# bubbler.net
KiCad netlist of a schematic drawn in EAGLE
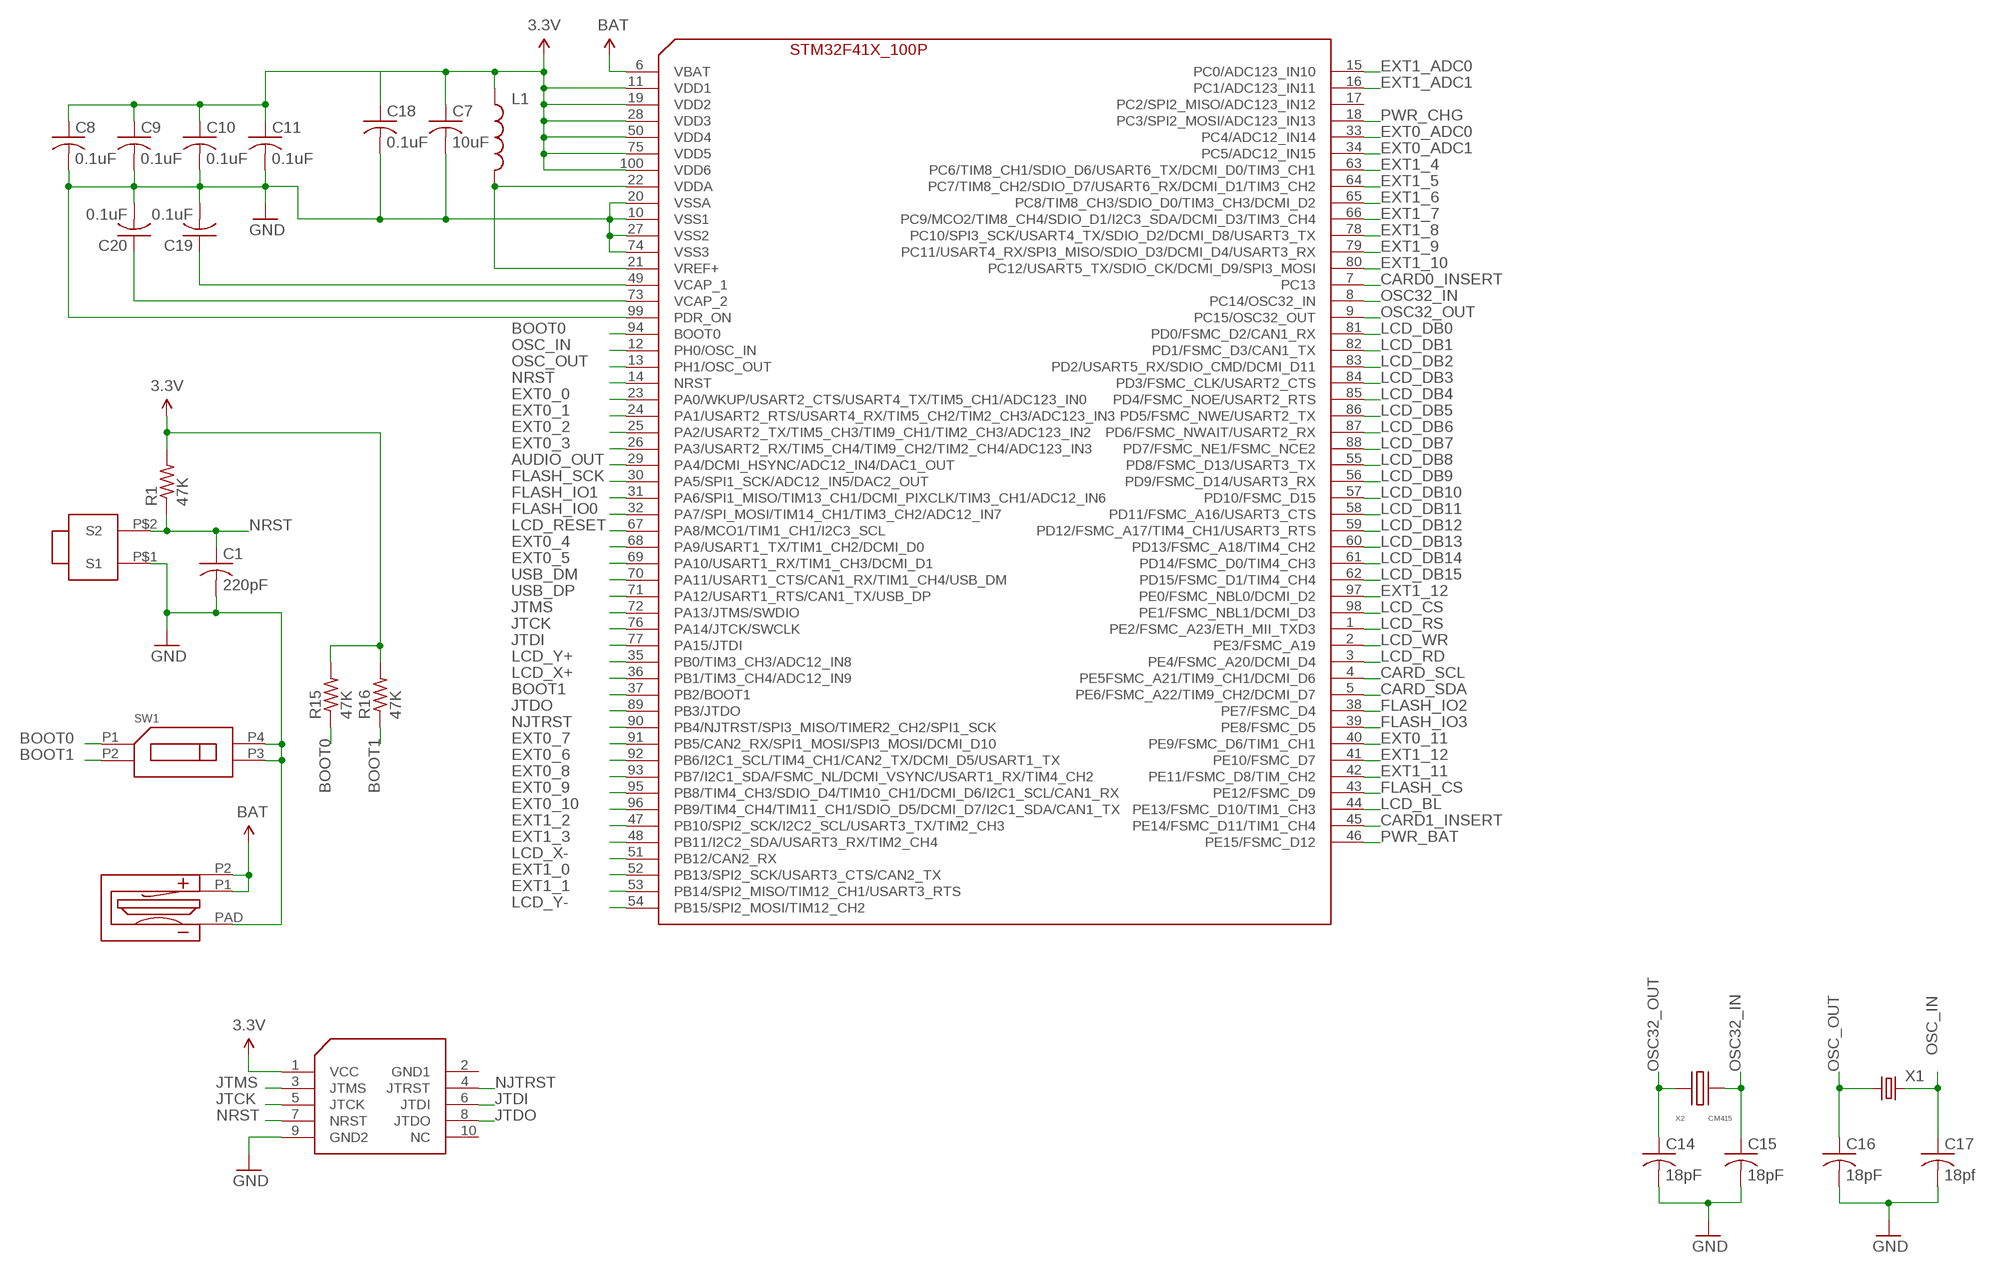
[diagram p0: schematic, sheet 1]
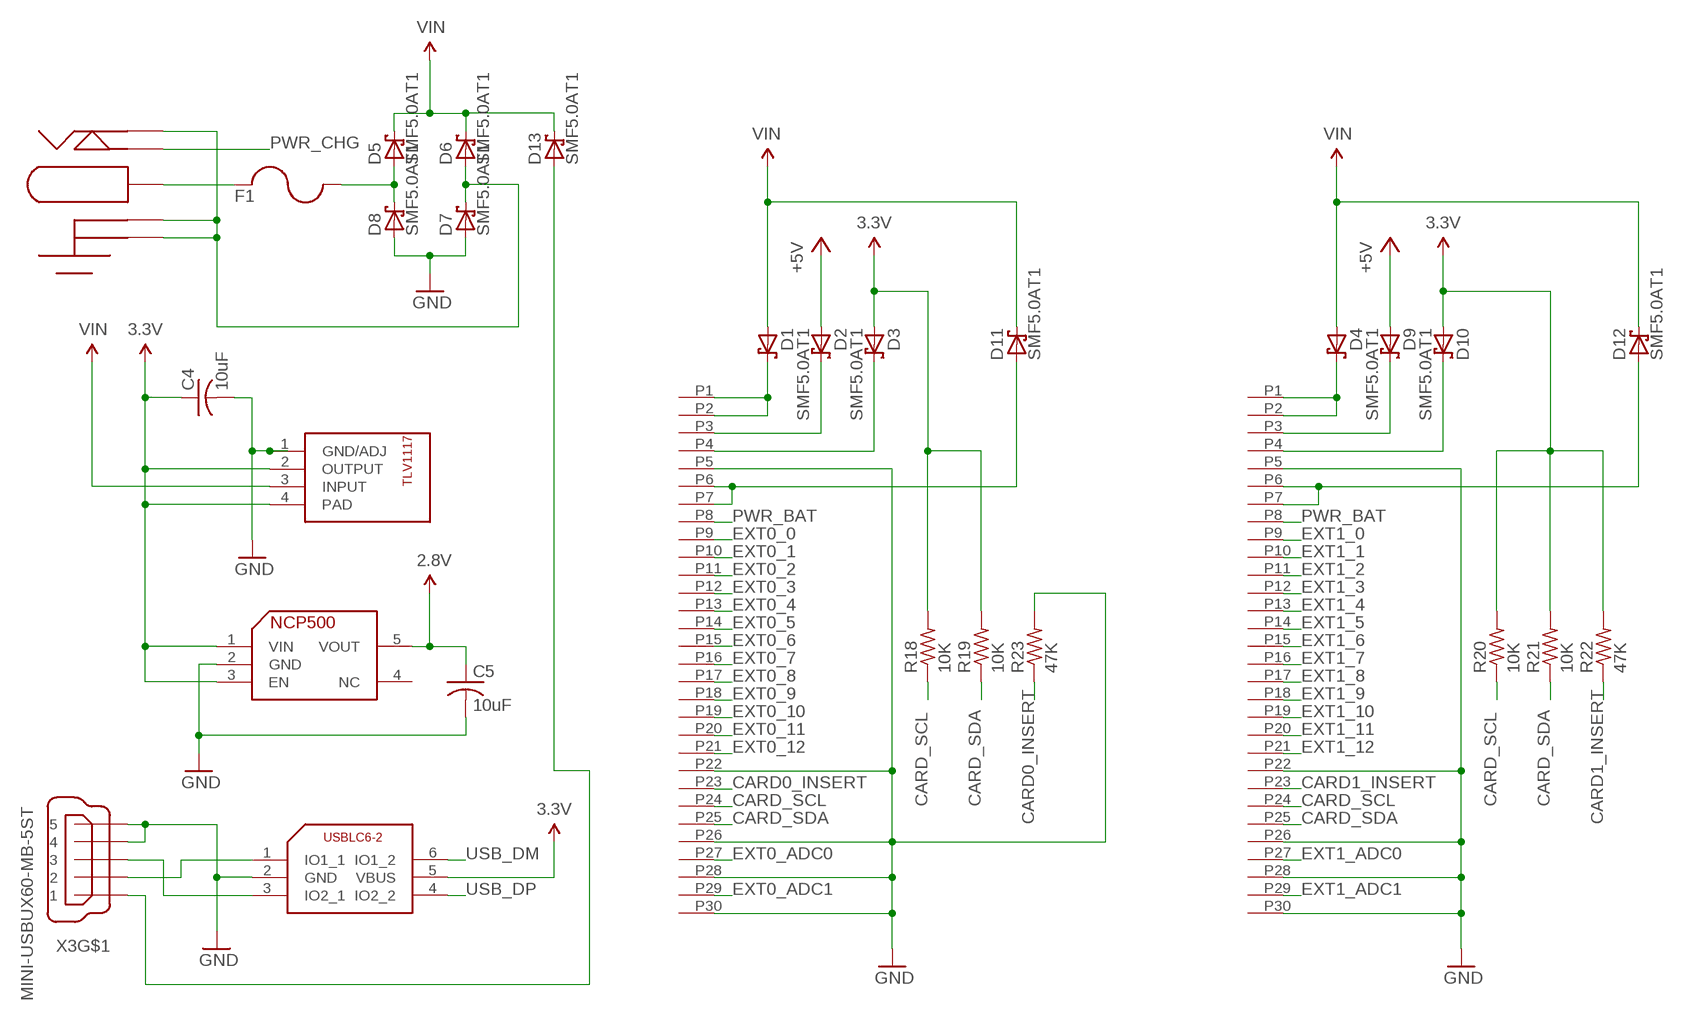
[diagram p1: schematic, sheet 2]
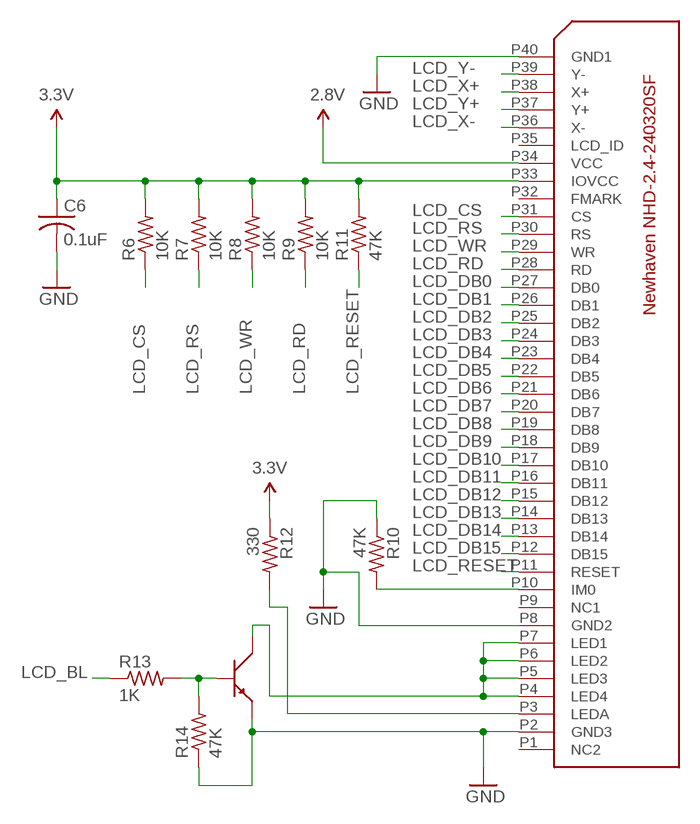
[diagram p2: schematic, sheet 3]
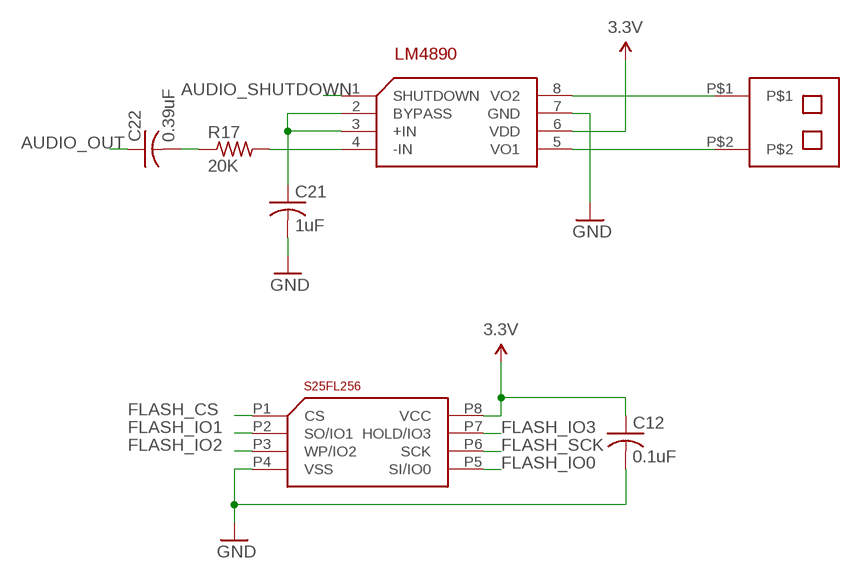
[diagram p3: schematic, sheet 4]

(export (version "E")
  (design (tool "Eeschema 10.0.6"))
  (components
    (comp (ref "B1")
      (value "BATTERY-LINX-HLD-001")
      (footprint "eagle-import:BATTERY-LINX-HLD-001")
      (libsource (lib "eagle-import") (part "BATTERY-LINX-HLD-001"))
    )
    (comp (ref "C1")
      (value "220pF")
      (footprint "eagle-import:C0402")
      (libsource (lib "eagle-import") (part "C-USC0402"))
    )
    (comp (ref "C7")
      (value "10uF")
      (footprint "eagle-import:C0805")
      (libsource (lib "eagle-import") (part "C-USC0805"))
    )
    (comp (ref "C8")
      (value "0.1uF")
      (footprint "eagle-import:C0402")
      (libsource (lib "eagle-import") (part "C-USC0402"))
    )
    (comp (ref "C9")
      (value "0.1uF")
      (footprint "eagle-import:C0402")
      (libsource (lib "eagle-import") (part "C-USC0402"))
    )
    (comp (ref "C10")
      (value "0.1uF")
      (footprint "eagle-import:C0402")
      (libsource (lib "eagle-import") (part "C-USC0402"))
    )
    (comp (ref "C11")
      (value "0.1uF")
      (footprint "eagle-import:C0402")
      (libsource (lib "eagle-import") (part "C-USC0402"))
    )
    (comp (ref "C14")
      (value "18pF")
      (footprint "eagle-import:C0402")
      (libsource (lib "eagle-import") (part "C-USC0402"))
    )
    (comp (ref "C15")
      (value "18pF")
      (footprint "eagle-import:C0402")
      (libsource (lib "eagle-import") (part "C-USC0402"))
    )
    (comp (ref "C16")
      (value "18pF")
      (footprint "eagle-import:C0402")
      (libsource (lib "eagle-import") (part "C-USC0402"))
    )
    (comp (ref "C17")
      (value "18pf")
      (footprint "eagle-import:C0402")
      (libsource (lib "eagle-import") (part "C-USC0402"))
    )
    (comp (ref "C18")
      (value "0.1uF")
      (footprint "eagle-import:C0402")
      (libsource (lib "eagle-import") (part "C-USC0402"))
    )
    (comp (ref "C19")
      (value "0.1uF")
      (footprint "eagle-import:C0402")
      (libsource (lib "eagle-import") (part "C-USC0402"))
    )
    (comp (ref "C20")
      (value "0.1uF")
      (footprint "eagle-import:C0402")
      (libsource (lib "eagle-import") (part "C-USC0402"))
    )
    (comp (ref "L1")
      (value "INDUCTOR0603")
      (footprint "eagle-import:0603")
      (libsource (lib "eagle-import") (part "INDUCTOR0603"))
    )
    (comp (ref "R1")
      (value "47K")
      (footprint "eagle-import:R0402")
      (libsource (lib "eagle-import") (part "R-US_R0402"))
    )
    (comp (ref "R15")
      (value "47K")
      (footprint "eagle-import:R0402")
      (libsource (lib "eagle-import") (part "R-US_R0402"))
    )
    (comp (ref "R16")
      (value "47K")
      (footprint "eagle-import:R0402")
      (libsource (lib "eagle-import") (part "R-US_R0402"))
    )
    (comp (ref "SW1")
      (value "SWITCH-DIP-GDH-02")
      (footprint "eagle-import:SWITCH-DIP-GDH-02")
      (libsource (lib "eagle-import") (part "SWITCH-DIP-GDH-02"))
    )
    (comp (ref "SW2")
      (value "ITT-SWITCH-KSS-G")
      (footprint "eagle-import:ITT-KSS-G")
      (libsource (lib "eagle-import") (part "ITT-SWITCH-KSS-G"))
    )
    (comp (ref "U$1")
      (value "STM32-JTAG-10P")
      (footprint "eagle-import:STM32-JTAG-10P")
      (libsource (lib "eagle-import") (part "STM32-JTAG-10P"))
    )
    (comp (ref "U1")
      (value "STM32F41X-100P")
      (footprint "eagle-import:TQFP100")
      (libsource (lib "eagle-import") (part "STM32F41X-100P"))
    )
    (comp (ref "X1")
      (value "CRYSTAL5X3")
      (footprint "eagle-import:CRYSTAL-SMD-5X3")
      (libsource (lib "eagle-import") (part "CRYSTAL5X3"))
    )
    (comp (ref "X2")
      (value "CM415")
      (footprint "eagle-import:CM415")
      (libsource (lib "eagle-import") (part "CM415"))
    )
    (comp (ref "C6")
      (value "0.1uF")
      (footprint "eagle-import:C0402")
      (libsource (lib "eagle-import") (part "C-USC0402"))
    )
    (comp (ref "R6")
      (value "10K")
      (footprint "eagle-import:R0402")
      (libsource (lib "eagle-import") (part "R-US_R0402"))
    )
    (comp (ref "R7")
      (value "10K")
      (footprint "eagle-import:R0402")
      (libsource (lib "eagle-import") (part "R-US_R0402"))
    )
    (comp (ref "R8")
      (value "10K")
      (footprint "eagle-import:R0402")
      (libsource (lib "eagle-import") (part "R-US_R0402"))
    )
    (comp (ref "R9")
      (value "10K")
      (footprint "eagle-import:R0402")
      (libsource (lib "eagle-import") (part "R-US_R0402"))
    )
    (comp (ref "R10")
      (value "47K")
      (footprint "eagle-import:R0402")
      (libsource (lib "eagle-import") (part "R-US_R0402"))
    )
    (comp (ref "R11")
      (value "47K")
      (footprint "eagle-import:R0402")
      (libsource (lib "eagle-import") (part "R-US_R0402"))
    )
    (comp (ref "R12")
      (value "330")
      (footprint "eagle-import:R1206")
      (libsource (lib "eagle-import") (part "R-US_R1206"))
    )
    (comp (ref "R13")
      (value "1K")
      (footprint "eagle-import:R0402")
      (libsource (lib "eagle-import") (part "R-US_R0402"))
    )
    (comp (ref "R14")
      (value "47K")
      (footprint "eagle-import:R0402")
      (libsource (lib "eagle-import") (part "R-US_R0402"))
    )
    (comp (ref "U$10")
      (value "NHD-2.4-240320SF")
      (footprint "eagle-import:MOLEX-534132-060")
      (libsource (lib "eagle-import") (part "NHD-2.4-240320SF"))
    )
    (comp (ref "U4")
      (value "BIPOLAR-PMBT6428")
      (footprint "eagle-import:DUBLIB_SOT23")
      (libsource (lib "eagle-import") (part "BIPOLAR-PMBT6428"))
    )
    (comp (ref "C4")
      (value "10uF")
      (footprint "eagle-import:C1206")
      (libsource (lib "eagle-import") (part "C-USC1206"))
    )
    (comp (ref "C5")
      (value "10uF")
      (footprint "eagle-import:C1206")
      (libsource (lib "eagle-import") (part "C-USC1206"))
    )
    (comp (ref "CARD0")
      (value "CONNECTOR-JAE-TX24-30F")
      (footprint "eagle-import:CONNECTOR-JAE-TX24-30")
      (libsource (lib "eagle-import") (part "CONNECTOR-JAE-TX24-30F"))
    )
    (comp (ref "CARD1")
      (value "CONNECTOR-JAE-TX24-30F")
      (footprint "eagle-import:CONNECTOR-JAE-TX24-30")
      (libsource (lib "eagle-import") (part "CONNECTOR-JAE-TX24-30F"))
    )
    (comp (ref "D1")
      (value "SCHOTTKY-DIODESMD")
      (footprint "eagle-import:SMB")
      (libsource (lib "eagle-import") (part "SCHOTTKY-DIODESMD"))
    )
    (comp (ref "D2")
      (value "SMF5.0AT1")
      (footprint "eagle-import:SOD123FL")
      (libsource (lib "eagle-import") (part "SMF5.0AT1"))
    )
    (comp (ref "D3")
      (value "SMF5.0AT1")
      (footprint "eagle-import:SOD123FL")
      (libsource (lib "eagle-import") (part "SMF5.0AT1"))
    )
    (comp (ref "D4")
      (value "SCHOTTKY-DIODESMD")
      (footprint "eagle-import:SMB")
      (libsource (lib "eagle-import") (part "SCHOTTKY-DIODESMD"))
    )
    (comp (ref "D5")
      (value "SMF5.0AT1")
      (footprint "eagle-import:SOD123FL")
      (libsource (lib "eagle-import") (part "SMF5.0AT1"))
    )
    (comp (ref "D6")
      (value "SMF5.0AT1")
      (footprint "eagle-import:SOD123FL")
      (libsource (lib "eagle-import") (part "SMF5.0AT1"))
    )
    (comp (ref "D7")
      (value "SMF5.0AT1")
      (footprint "eagle-import:SOD123FL")
      (libsource (lib "eagle-import") (part "SMF5.0AT1"))
    )
    (comp (ref "D8")
      (value "SMF5.0AT1")
      (footprint "eagle-import:SOD123FL")
      (libsource (lib "eagle-import") (part "SMF5.0AT1"))
    )
    (comp (ref "D9")
      (value "SMF5.0AT1")
      (footprint "eagle-import:SOD123FL")
      (libsource (lib "eagle-import") (part "SMF5.0AT1"))
    )
    (comp (ref "D10")
      (value "SMF5.0AT1")
      (footprint "eagle-import:SOD123FL")
      (libsource (lib "eagle-import") (part "SMF5.0AT1"))
    )
    (comp (ref "D11")
      (value "SMF5.0AT1")
      (footprint "eagle-import:SOD123FL")
      (libsource (lib "eagle-import") (part "SMF5.0AT1"))
    )
    (comp (ref "D12")
      (value "SMF5.0AT1")
      (footprint "eagle-import:SOD123FL")
      (libsource (lib "eagle-import") (part "SMF5.0AT1"))
    )
    (comp (ref "D13")
      (value "SMF5.0AT1")
      (footprint "eagle-import:SOD123FL")
      (libsource (lib "eagle-import") (part "SMF5.0AT1"))
    )
    (comp (ref "F1")
      (value "BOURNES-PTC-MF-SMXXXMF-SM030")
      (footprint "eagle-import:MF-SM030")
      (libsource (lib "eagle-import") (part "BOURNES-PTC-MF-SMXXXMF-SM030"))
    )
    (comp (ref "R18")
      (value "10K")
      (footprint "eagle-import:R0402")
      (libsource (lib "eagle-import") (part "R-US_R0402"))
    )
    (comp (ref "R19")
      (value "10K")
      (footprint "eagle-import:R0402")
      (libsource (lib "eagle-import") (part "R-US_R0402"))
    )
    (comp (ref "R20")
      (value "10K")
      (footprint "eagle-import:R0402")
      (libsource (lib "eagle-import") (part "R-US_R0402"))
    )
    (comp (ref "R21")
      (value "10K")
      (footprint "eagle-import:R0402")
      (libsource (lib "eagle-import") (part "R-US_R0402"))
    )
    (comp (ref "R22")
      (value "47K")
      (footprint "eagle-import:R0402")
      (libsource (lib "eagle-import") (part "R-US_R0402"))
    )
    (comp (ref "R23")
      (value "47K")
      (footprint "eagle-import:R0402")
      (libsource (lib "eagle-import") (part "R-US_R0402"))
    )
    (comp (ref "U$2")
      (value "DCJACK-CUI-PJ051AH")
      (footprint "eagle-import:DCJACK_CUI_PJ012B")
      (libsource (lib "eagle-import") (part "DCJACK-CUI-PJ051AH"))
    )
    (comp (ref "U$7")
      (value "NCP500")
      (footprint "eagle-import:SOT23-5L")
      (libsource (lib "eagle-import") (part "NCP500"))
    )
    (comp (ref "U5")
      (value "USBLC6-2")
      (footprint "eagle-import:SOT23-6L")
      (libsource (lib "eagle-import") (part "USBLC6-2"))
    )
    (comp (ref "U6")
      (value "TLV1117")
      (footprint "eagle-import:SOT223")
      (libsource (lib "eagle-import") (part "TLV1117"))
    )
    (comp (ref "X3")
      (value "MINI-USBUX60-MB-5ST")
      (footprint "eagle-import:DUBLIB_UX60-MB-5ST")
      (libsource (lib "eagle-import") (part "MINI-USBUX60-MB-5ST"))
    )
    (comp (ref "C12")
      (value "0.1uF")
      (footprint "eagle-import:C0402")
      (libsource (lib "eagle-import") (part "C-USC0402"))
    )
    (comp (ref "C21")
      (value "1uF")
      (footprint "eagle-import:C0402")
      (libsource (lib "eagle-import") (part "C-USC0402"))
    )
    (comp (ref "C22")
      (value "0.39uF")
      (footprint "eagle-import:C0402")
      (libsource (lib "eagle-import") (part "C-USC0402"))
    )
    (comp (ref "R17")
      (value "20K")
      (footprint "eagle-import:R0402")
      (libsource (lib "eagle-import") (part "R-US_R0402"))
    )
    (comp (ref "U2")
      (value "SPANSION-S25FL256")
      (footprint "eagle-import:SPANSION-WSON-8")
      (libsource (lib "eagle-import") (part "SPANSION-S25FL256"))
    )
    (comp (ref "U3")
      (value "LM4890")
      (footprint "eagle-import:TSSOP8")
      (libsource (lib "eagle-import") (part "LM4890"))
    )
    (comp (ref "U7")
      (value "MOLEX-1.25-WTB-RA-CONN-2POS")
      (footprint "eagle-import:MOLEX-1.25WTB-RA-CONN")
      (libsource (lib "eagle-import") (part "MOLEX-1.25-WTB-RA-CONN-2POS"))
    )
  )
  (nets
    (net (code "1") (name "+5V") (class "Default")
      (node (ref "D2") (pin "A") (pinfunction "A_A") (pintype "passive"))
      (node (ref "D9") (pin "A") (pinfunction "A_A") (pintype "passive"))
    )
    (net (code "2") (name "2.8V") (class "Default")
      (node (ref "C5") (pin "1") (pinfunction "1_1") (pintype "passive"))
      (node (ref "U$10") (pin "P34") (pinfunction "VCC_P34") (pintype "bidirectional"))
      (node (ref "U$7") (pin "5") (pinfunction "VOUT_5") (pintype "bidirectional"))
    )
    (net (code "3") (name "3.3V") (class "Default")
      (node (ref "C10") (pin "1") (pinfunction "1_1") (pintype "passive"))
      (node (ref "C11") (pin "1") (pinfunction "1_1") (pintype "passive"))
      (node (ref "C12") (pin "1") (pinfunction "1_1") (pintype "passive"))
      (node (ref "C18") (pin "1") (pinfunction "1_1") (pintype "passive"))
      (node (ref "C4") (pin "1") (pinfunction "1_1") (pintype "passive"))
      (node (ref "C6") (pin "1") (pinfunction "1_1") (pintype "passive"))
      (node (ref "C7") (pin "1") (pinfunction "1_1") (pintype "passive"))
      (node (ref "C8") (pin "1") (pinfunction "1_1") (pintype "passive"))
      (node (ref "C9") (pin "1") (pinfunction "1_1") (pintype "passive"))
      (node (ref "D10") (pin "A") (pinfunction "A_A") (pintype "passive"))
      (node (ref "D3") (pin "A") (pinfunction "A_A") (pintype "passive"))
      (node (ref "L1") (pin "1") (pinfunction "1_1") (pintype "passive"))
      (node (ref "R1") (pin "2") (pinfunction "2_2") (pintype "passive"))
      (node (ref "R11") (pin "2") (pinfunction "2_2") (pintype "passive"))
      (node (ref "R12") (pin "1") (pinfunction "1_1") (pintype "passive"))
      (node (ref "R15") (pin "2") (pinfunction "2_2") (pintype "passive"))
      (node (ref "R16") (pin "2") (pinfunction "2_2") (pintype "passive"))
      (node (ref "R18") (pin "2") (pinfunction "2_2") (pintype "passive"))
      (node (ref "R19") (pin "2") (pinfunction "2_2") (pintype "passive"))
      (node (ref "R20") (pin "2") (pinfunction "2_2") (pintype "passive"))
      (node (ref "R21") (pin "2") (pinfunction "2_2") (pintype "passive"))
      (node (ref "R22") (pin "2") (pinfunction "2_2") (pintype "passive"))
      (node (ref "R6") (pin "2") (pinfunction "2_2") (pintype "passive"))
      (node (ref "R7") (pin "2") (pinfunction "2_2") (pintype "passive"))
      (node (ref "R8") (pin "2") (pinfunction "2_2") (pintype "passive"))
      (node (ref "R9") (pin "2") (pinfunction "2_2") (pintype "passive"))
      (node (ref "U$1") (pin "1") (pinfunction "VCC_1") (pintype "bidirectional"))
      (node (ref "U$10") (pin "P33") (pinfunction "IOVCC_P33") (pintype "bidirectional"))
      (node (ref "U$7") (pin "1") (pinfunction "VIN_1") (pintype "bidirectional"))
      (node (ref "U$7") (pin "3") (pinfunction "EN_3") (pintype "bidirectional"))
      (node (ref "U1") (pin "100") (pinfunction "VDD6_100") (pintype "bidirectional"))
      (node (ref "U1") (pin "11") (pinfunction "VDD1_11") (pintype "bidirectional"))
      (node (ref "U1") (pin "19") (pinfunction "VDD2_19") (pintype "bidirectional"))
      (node (ref "U1") (pin "28") (pinfunction "VDD3_28") (pintype "bidirectional"))
      (node (ref "U1") (pin "50") (pinfunction "VDD4_50") (pintype "bidirectional"))
      (node (ref "U1") (pin "75") (pinfunction "VDD5_75") (pintype "bidirectional"))
      (node (ref "U2") (pin "P8") (pinfunction "VCC_P8") (pintype "bidirectional"))
      (node (ref "U3") (pin "6") (pinfunction "VDD_6") (pintype "bidirectional"))
      (node (ref "U5") (pin "5") (pinfunction "VBUS_5") (pintype "bidirectional"))
      (node (ref "U6") (pin "2") (pinfunction "OUTPUT_2") (pintype "bidirectional"))
      (node (ref "U6") (pin "4") (pinfunction "PAD_4") (pintype "bidirectional"))
    )
    (net (code "4") (name "AUDIO_OUT") (class "Default")
      (node (ref "C22") (pin "1") (pinfunction "1_1") (pintype "passive"))
      (node (ref "U1") (pin "29") (pinfunction "PA4/DCMI_HSYNC/ADC12_IN4/DAC1_OUT_29") (pintype "bidirectional"))
    )
    (net (code "5") (name "AUDIO_SHUTDOWN") (class "Default")
      (node (ref "U3") (pin "1") (pinfunction "SHUTDOWN_1") (pintype "bidirectional"))
    )
    (net (code "6") (name "BAT") (class "Default")
      (node (ref "B1") (pin "P1") (pinfunction "BAT1_P1") (pintype "power_in"))
      (node (ref "B1") (pin "P2") (pinfunction "BAT2_P2") (pintype "power_in"))
      (node (ref "U1") (pin "6") (pinfunction "VBAT_6") (pintype "bidirectional"))
    )
    (net (code "7") (name "BOOT0") (class "Default")
      (node (ref "R15") (pin "1") (pinfunction "1_1") (pintype "passive"))
      (node (ref "SW1") (pin "P1") (pinfunction "SW0_0_P1") (pintype "bidirectional"))
      (node (ref "U1") (pin "94") (pinfunction "BOOT0_94") (pintype "bidirectional"))
    )
    (net (code "8") (name "BOOT1") (class "Default")
      (node (ref "R16") (pin "1") (pinfunction "1_1") (pintype "passive"))
      (node (ref "SW1") (pin "P2") (pinfunction "SW1_0_P2") (pintype "bidirectional"))
      (node (ref "U1") (pin "37") (pinfunction "PB2/BOOT1_37") (pintype "bidirectional"))
    )
    (net (code "9") (name "CARD0_INSERT") (class "Default")
      (node (ref "CARD0") (pin "P23") (pinfunction "P23_P23") (pintype "bidirectional"))
      (node (ref "R23") (pin "1") (pinfunction "1_1") (pintype "passive"))
      (node (ref "U1") (pin "7") (pinfunction "PC13_7") (pintype "bidirectional"))
    )
    (net (code "10") (name "CARD1_INSERT") (class "Default")
      (node (ref "CARD1") (pin "P23") (pinfunction "P23_P23") (pintype "bidirectional"))
      (node (ref "R22") (pin "1") (pinfunction "1_1") (pintype "passive"))
      (node (ref "U1") (pin "45") (pinfunction "PE14/FSMC_D11/TIM1_CH4_45") (pintype "bidirectional"))
    )
    (net (code "11") (name "CARD_SCL") (class "Default")
      (node (ref "CARD0") (pin "P24") (pinfunction "P24_P24") (pintype "bidirectional"))
      (node (ref "CARD1") (pin "P24") (pinfunction "P24_P24") (pintype "bidirectional"))
      (node (ref "R18") (pin "1") (pinfunction "1_1") (pintype "passive"))
      (node (ref "R20") (pin "1") (pinfunction "1_1") (pintype "passive"))
      (node (ref "U1") (pin "4") (pinfunction "PE5FSMC_A21/TIM9_CH1/DCMI_D6_4") (pintype "bidirectional"))
    )
    (net (code "12") (name "CARD_SDA") (class "Default")
      (node (ref "CARD0") (pin "P25") (pinfunction "P25_P25") (pintype "bidirectional"))
      (node (ref "CARD1") (pin "P25") (pinfunction "P25_P25") (pintype "bidirectional"))
      (node (ref "R19") (pin "1") (pinfunction "1_1") (pintype "passive"))
      (node (ref "R21") (pin "1") (pinfunction "1_1") (pintype "passive"))
      (node (ref "U1") (pin "5") (pinfunction "PE6/FSMC_A22/TIM9_CH2/DCMI_D7_5") (pintype "bidirectional"))
    )
    (net (code "13") (name "EXT0_0") (class "Default")
      (node (ref "CARD0") (pin "P9") (pinfunction "P9_P9") (pintype "bidirectional"))
      (node (ref "U1") (pin "23") (pinfunction "PA0/WKUP/USART2_CTS/USART4_TX/TIM5_CH1/ADC123_IN0_23") (pintype "bidirectional"))
    )
    (net (code "14") (name "EXT0_1") (class "Default")
      (node (ref "CARD0") (pin "P10") (pinfunction "P10_P10") (pintype "bidirectional"))
      (node (ref "U1") (pin "24") (pinfunction "PA1/USART2_RTS/USART4_RX/TIM5_CH2/TIM2_CH3/ADC123_IN3_24") (pintype "bidirectional"))
    )
    (net (code "15") (name "EXT0_2") (class "Default")
      (node (ref "CARD0") (pin "P11") (pinfunction "P11_P11") (pintype "bidirectional"))
      (node (ref "U1") (pin "25") (pinfunction "PA2/USART2_TX/TIM5_CH3/TIM9_CH1/TIM2_CH3/ADC123_IN2_25") (pintype "bidirectional"))
    )
    (net (code "16") (name "EXT0_3") (class "Default")
      (node (ref "CARD0") (pin "P12") (pinfunction "P12_P12") (pintype "bidirectional"))
      (node (ref "U1") (pin "26") (pinfunction "PA3/USART2_RX/TIM5_CH4/TIM9_CH2/TIM2_CH4/ADC123_IN3_26") (pintype "bidirectional"))
    )
    (net (code "17") (name "EXT0_4") (class "Default")
      (node (ref "CARD0") (pin "P13") (pinfunction "P13_P13") (pintype "bidirectional"))
      (node (ref "U1") (pin "68") (pinfunction "PA9/USART1_TX/TIM1_CH2/DCMI_D0_68") (pintype "bidirectional"))
    )
    (net (code "18") (name "EXT0_5") (class "Default")
      (node (ref "CARD0") (pin "P14") (pinfunction "P14_P14") (pintype "bidirectional"))
      (node (ref "U1") (pin "69") (pinfunction "PA10/USART1_RX/TIM1_CH3/DCMI_D1_69") (pintype "bidirectional"))
    )
    (net (code "19") (name "EXT0_6") (class "Default")
      (node (ref "CARD0") (pin "P15") (pinfunction "P15_P15") (pintype "bidirectional"))
      (node (ref "U1") (pin "92") (pinfunction "PB6/I2C1_SCL/TIM4_CH1/CAN2_TX/DCMI_D5/USART1_TX_92") (pintype "bidirectional"))
    )
    (net (code "20") (name "EXT0_7") (class "Default")
      (node (ref "CARD0") (pin "P16") (pinfunction "P16_P16") (pintype "bidirectional"))
      (node (ref "U1") (pin "91") (pinfunction "PB5/CAN2_RX/SPI1_MOSI/SPI3_MOSI/DCMI_D10_91") (pintype "bidirectional"))
    )
    (net (code "21") (name "EXT0_8") (class "Default")
      (node (ref "CARD0") (pin "P17") (pinfunction "P17_P17") (pintype "bidirectional"))
      (node (ref "U1") (pin "93") (pinfunction "PB7/I2C1_SDA/FSMC_NL/DCMI_VSYNC/USART1_RX/TIM4_CH2_93") (pintype "bidirectional"))
    )
    (net (code "22") (name "EXT0_9") (class "Default")
      (node (ref "CARD0") (pin "P18") (pinfunction "P18_P18") (pintype "bidirectional"))
      (node (ref "U1") (pin "95") (pinfunction "PB8/TIM4_CH3/SDIO_D4/TIM10_CH1/DCMI_D6/I2C1_SCL/CAN1_RX_95") (pintype "bidirectional"))
    )
    (net (code "23") (name "EXT0_10") (class "Default")
      (node (ref "CARD0") (pin "P19") (pinfunction "P19_P19") (pintype "bidirectional"))
      (node (ref "U1") (pin "96") (pinfunction "PB9/TIM4_CH4/TIM11_CH1/SDIO_D5/DCMI_D7/I2C1_SDA/CAN1_TX_96") (pintype "bidirectional"))
    )
    (net (code "24") (name "EXT0_11") (class "Default")
      (node (ref "CARD0") (pin "P20") (pinfunction "P20_P20") (pintype "bidirectional"))
      (node (ref "U1") (pin "40") (pinfunction "PE9/FSMC_D6/TIM1_CH1_40") (pintype "bidirectional"))
    )
    (net (code "25") (name "EXT0_12") (class "Default")
      (node (ref "CARD0") (pin "P21") (pinfunction "P21_P21") (pintype "bidirectional"))
    )
    (net (code "26") (name "EXT0_ADC0") (class "Default")
      (node (ref "CARD0") (pin "P27") (pinfunction "P27_P27") (pintype "bidirectional"))
      (node (ref "U1") (pin "33") (pinfunction "PC4/ADC12_IN14_33") (pintype "bidirectional"))
    )
    (net (code "27") (name "EXT0_ADC1") (class "Default")
      (node (ref "CARD0") (pin "P29") (pinfunction "P29_P29") (pintype "bidirectional"))
      (node (ref "U1") (pin "34") (pinfunction "PC5/ADC12_IN15_34") (pintype "bidirectional"))
    )
    (net (code "28") (name "EXT1_0") (class "Default")
      (node (ref "CARD1") (pin "P9") (pinfunction "P9_P9") (pintype "bidirectional"))
      (node (ref "U1") (pin "52") (pinfunction "PB13/SPI2_SCK/USART3_CTS/CAN2_TX_52") (pintype "bidirectional"))
    )
    (net (code "29") (name "EXT1_1") (class "Default")
      (node (ref "CARD1") (pin "P10") (pinfunction "P10_P10") (pintype "bidirectional"))
      (node (ref "U1") (pin "53") (pinfunction "PB14/SPI2_MISO/TIM12_CH1/USART3_RTS_53") (pintype "bidirectional"))
    )
    (net (code "30") (name "EXT1_2") (class "Default")
      (node (ref "CARD1") (pin "P11") (pinfunction "P11_P11") (pintype "bidirectional"))
      (node (ref "U1") (pin "47") (pinfunction "PB10/SPI2_SCK/I2C2_SCL/USART3_TX/TIM2_CH3_47") (pintype "bidirectional"))
    )
    (net (code "31") (name "EXT1_3") (class "Default")
      (node (ref "CARD1") (pin "P12") (pinfunction "P12_P12") (pintype "bidirectional"))
      (node (ref "U1") (pin "48") (pinfunction "PB11/I2C2_SDA/USART3_RX/TIM2_CH4_48") (pintype "bidirectional"))
    )
    (net (code "32") (name "EXT1_4") (class "Default")
      (node (ref "CARD1") (pin "P13") (pinfunction "P13_P13") (pintype "bidirectional"))
      (node (ref "U1") (pin "63") (pinfunction "PC6/TIM8_CH1/SDIO_D6/USART6_TX/DCMI_D0/TIM3_CH1_63") (pintype "bidirectional"))
    )
    (net (code "33") (name "EXT1_5") (class "Default")
      (node (ref "CARD1") (pin "P14") (pinfunction "P14_P14") (pintype "bidirectional"))
      (node (ref "U1") (pin "64") (pinfunction "PC7/TIM8_CH2/SDIO_D7/USART6_RX/DCMI_D1/TIM3_CH2_64") (pintype "bidirectional"))
    )
    (net (code "34") (name "EXT1_6") (class "Default")
      (node (ref "CARD1") (pin "P15") (pinfunction "P15_P15") (pintype "bidirectional"))
      (node (ref "U1") (pin "65") (pinfunction "PC8/TIM8_CH3/SDIO_D0/TIM3_CH3/DCMI_D2_65") (pintype "bidirectional"))
    )
    (net (code "35") (name "EXT1_7") (class "Default")
      (node (ref "CARD1") (pin "P16") (pinfunction "P16_P16") (pintype "bidirectional"))
      (node (ref "U1") (pin "66") (pinfunction "PC9/MCO2/TIM8_CH4/SDIO_D1/I2C3_SDA/DCMI_D3/TIM3_CH4_66") (pintype "bidirectional"))
    )
    (net (code "36") (name "EXT1_8") (class "Default")
      (node (ref "CARD1") (pin "P17") (pinfunction "P17_P17") (pintype "bidirectional"))
      (node (ref "U1") (pin "78") (pinfunction "PC10/SPI3_SCK/USART4_TX/SDIO_D2/DCMI_D8/USART3_TX_78") (pintype "bidirectional"))
    )
    (net (code "37") (name "EXT1_9") (class "Default")
      (node (ref "CARD1") (pin "P18") (pinfunction "P18_P18") (pintype "bidirectional"))
      (node (ref "U1") (pin "79") (pinfunction "PC11/USART4_RX/SPI3_MISO/SDIO_D3/DCMI_D4/USART3_RX_79") (pintype "bidirectional"))
    )
    (net (code "38") (name "EXT1_10") (class "Default")
      (node (ref "CARD1") (pin "P19") (pinfunction "P19_P19") (pintype "bidirectional"))
      (node (ref "U1") (pin "80") (pinfunction "PC12/USART5_TX/SDIO_CK/DCMI_D9/SPI3_MOSI_80") (pintype "bidirectional"))
    )
    (net (code "39") (name "EXT1_11") (class "Default")
      (node (ref "CARD1") (pin "P20") (pinfunction "P20_P20") (pintype "bidirectional"))
      (node (ref "U1") (pin "42") (pinfunction "PE11/FSMC_D8/TIM_CH2_42") (pintype "bidirectional"))
    )
    (net (code "40") (name "EXT1_12") (class "Default")
      (node (ref "CARD1") (pin "P21") (pinfunction "P21_P21") (pintype "bidirectional"))
      (node (ref "U1") (pin "41") (pinfunction "PE10/FSMC_D7_41") (pintype "bidirectional"))
      (node (ref "U1") (pin "97") (pinfunction "PE0/FSMC_NBL0/DCMI_D2_97") (pintype "bidirectional"))
    )
    (net (code "41") (name "EXT1_ADC0") (class "Default")
      (node (ref "CARD1") (pin "P27") (pinfunction "P27_P27") (pintype "bidirectional"))
      (node (ref "U1") (pin "15") (pinfunction "PC0/ADC123_IN10_15") (pintype "bidirectional"))
    )
    (net (code "42") (name "EXT1_ADC1") (class "Default")
      (node (ref "CARD1") (pin "P29") (pinfunction "P29_P29") (pintype "bidirectional"))
      (node (ref "U1") (pin "16") (pinfunction "PC1/ADC123_IN11_16") (pintype "bidirectional"))
    )
    (net (code "43") (name "FLASH_CS") (class "Default")
      (node (ref "U1") (pin "43") (pinfunction "PE12/FSMC_D9_43") (pintype "bidirectional"))
      (node (ref "U2") (pin "P1") (pinfunction "CS_P1") (pintype "bidirectional"))
    )
    (net (code "44") (name "FLASH_IO0") (class "Default")
      (node (ref "U1") (pin "32") (pinfunction "PA7/SPI_MOSI/TIM14_CH1/TIM3_CH2/ADC12_IN7_32") (pintype "bidirectional"))
      (node (ref "U2") (pin "P5") (pinfunction "SI/IO0_P5") (pintype "bidirectional"))
    )
    (net (code "45") (name "FLASH_IO1") (class "Default")
      (node (ref "U1") (pin "31") (pinfunction "PA6/SPI1_MISO/TIM13_CH1/DCMI_PIXCLK/TIM3_CH1/ADC12_IN6_31") (pintype "bidirectional"))
      (node (ref "U2") (pin "P2") (pinfunction "SO/IO1_P2") (pintype "bidirectional"))
    )
    (net (code "46") (name "FLASH_IO2") (class "Default")
      (node (ref "U1") (pin "38") (pinfunction "PE7/FSMC_D4_38") (pintype "bidirectional"))
      (node (ref "U2") (pin "P3") (pinfunction "WP/IO2_P3") (pintype "bidirectional"))
    )
    (net (code "47") (name "FLASH_IO3") (class "Default")
      (node (ref "U1") (pin "39") (pinfunction "PE8/FSMC_D5_39") (pintype "bidirectional"))
      (node (ref "U2") (pin "P7") (pinfunction "HOLD/IO3_P7") (pintype "bidirectional"))
    )
    (net (code "48") (name "FLASH_SCK") (class "Default")
      (node (ref "U1") (pin "30") (pinfunction "PA5/SPI1_SCK/ADC12_IN5/DAC2_OUT_30") (pintype "bidirectional"))
      (node (ref "U2") (pin "P6") (pinfunction "SCK_P6") (pintype "bidirectional"))
    )
    (net (code "49") (name "GND") (class "Default")
      (node (ref "B1") (pin "PAD") (pinfunction "GND_PAD") (pintype "power_in"))
      (node (ref "C1") (pin "2") (pinfunction "2_2") (pintype "passive"))
      (node (ref "C10") (pin "2") (pinfunction "2_2") (pintype "passive"))
      (node (ref "C11") (pin "2") (pinfunction "2_2") (pintype "passive"))
      (node (ref "C12") (pin "2") (pinfunction "2_2") (pintype "passive"))
      (node (ref "C14") (pin "2") (pinfunction "2_2") (pintype "passive"))
      (node (ref "C15") (pin "2") (pinfunction "2_2") (pintype "passive"))
      (node (ref "C16") (pin "2") (pinfunction "2_2") (pintype "passive"))
      (node (ref "C17") (pin "2") (pinfunction "2_2") (pintype "passive"))
      (node (ref "C18") (pin "2") (pinfunction "2_2") (pintype "passive"))
      (node (ref "C19") (pin "2") (pinfunction "2_2") (pintype "passive"))
      (node (ref "C20") (pin "2") (pinfunction "2_2") (pintype "passive"))
      (node (ref "C21") (pin "2") (pinfunction "2_2") (pintype "passive"))
      (node (ref "C4") (pin "2") (pinfunction "2_2") (pintype "passive"))
      (node (ref "C5") (pin "2") (pinfunction "2_2") (pintype "passive"))
      (node (ref "C6") (pin "2") (pinfunction "2_2") (pintype "passive"))
      (node (ref "C7") (pin "2") (pinfunction "2_2") (pintype "passive"))
      (node (ref "C8") (pin "2") (pinfunction "2_2") (pintype "passive"))
      (node (ref "C9") (pin "2") (pinfunction "2_2") (pintype "passive"))
      (node (ref "CARD0") (pin "P22") (pinfunction "P22_P22") (pintype "bidirectional"))
      (node (ref "CARD0") (pin "P26") (pinfunction "P26_P26") (pintype "bidirectional"))
      (node (ref "CARD0") (pin "P28") (pinfunction "P28_P28") (pintype "bidirectional"))
      (node (ref "CARD0") (pin "P30") (pinfunction "P30_P30") (pintype "bidirectional"))
      (node (ref "CARD0") (pin "P5") (pinfunction "P5_P5") (pintype "bidirectional"))
      (node (ref "CARD1") (pin "P22") (pinfunction "P22_P22") (pintype "bidirectional"))
      (node (ref "CARD1") (pin "P26") (pinfunction "P26_P26") (pintype "bidirectional"))
      (node (ref "CARD1") (pin "P28") (pinfunction "P28_P28") (pintype "bidirectional"))
      (node (ref "CARD1") (pin "P30") (pinfunction "P30_P30") (pintype "bidirectional"))
      (node (ref "CARD1") (pin "P5") (pinfunction "P5_P5") (pintype "bidirectional"))
      (node (ref "D7") (pin "A") (pinfunction "A_A") (pintype "passive"))
      (node (ref "D8") (pin "A") (pinfunction "A_A") (pintype "passive"))
      (node (ref "R10") (pin "1") (pinfunction "1_1") (pintype "passive"))
      (node (ref "R14") (pin "1") (pinfunction "1_1") (pintype "passive"))
      (node (ref "R23") (pin "2") (pinfunction "2_2") (pintype "passive"))
      (node (ref "SW1") (pin "P3") (pinfunction "SW1_1_P3") (pintype "bidirectional"))
      (node (ref "SW1") (pin "P4") (pinfunction "SW0_1_P4") (pintype "bidirectional"))
      (node (ref "SW2") (pin "P$1") (pinfunction "S1_P$1") (pintype "bidirectional"))
      (node (ref "U$1") (pin "9") (pinfunction "GND2_9") (pintype "bidirectional"))
      (node (ref "U$10") (pin "P2") (pinfunction "GND3_P2") (pintype "bidirectional"))
      (node (ref "U$10") (pin "P40") (pinfunction "GND1_P40") (pintype "bidirectional"))
      (node (ref "U$10") (pin "P8") (pinfunction "GND2_P8") (pintype "bidirectional"))
      (node (ref "U$7") (pin "2") (pinfunction "GND_2") (pintype "bidirectional"))
      (node (ref "U1") (pin "10") (pinfunction "VSS1_10") (pintype "bidirectional"))
      (node (ref "U1") (pin "20") (pinfunction "VSSA_20") (pintype "bidirectional"))
      (node (ref "U1") (pin "27") (pinfunction "VSS2_27") (pintype "bidirectional"))
      (node (ref "U1") (pin "74") (pinfunction "VSS3_74") (pintype "bidirectional"))
      (node (ref "U1") (pin "99") (pinfunction "PDR_ON_99") (pintype "bidirectional"))
      (node (ref "U2") (pin "P4") (pinfunction "VSS_P4") (pintype "bidirectional"))
      (node (ref "U3") (pin "7") (pinfunction "GND_7") (pintype "bidirectional"))
      (node (ref "U4") (pin "2") (pinfunction "2_2") (pintype "bidirectional"))
      (node (ref "U5") (pin "2") (pinfunction "GND_2") (pintype "bidirectional"))
      (node (ref "U6") (pin "1") (pinfunction "GND/ADJ_1") (pintype "bidirectional"))
      (node (ref "X3") (pin "4") (pinfunction "4_4") (pintype "input"))
      (node (ref "X3") (pin "5") (pinfunction "5_5") (pintype "input"))
    )
    (net (code "50") (name "JTCK") (class "Default")
      (node (ref "U$1") (pin "5") (pinfunction "JTCK_5") (pintype "bidirectional"))
      (node (ref "U1") (pin "76") (pinfunction "PA14/JTCK/SWCLK_76") (pintype "bidirectional"))
    )
    (net (code "51") (name "JTDI") (class "Default")
      (node (ref "U$1") (pin "6") (pinfunction "JTDI_6") (pintype "bidirectional"))
      (node (ref "U1") (pin "77") (pinfunction "PA15/JTDI_77") (pintype "bidirectional"))
    )
    (net (code "52") (name "JTDO") (class "Default")
      (node (ref "U$1") (pin "8") (pinfunction "JTDO_8") (pintype "bidirectional"))
      (node (ref "U1") (pin "89") (pinfunction "PB3/JTDO_89") (pintype "bidirectional"))
    )
    (net (code "53") (name "JTMS") (class "Default")
      (node (ref "U$1") (pin "3") (pinfunction "JTMS_3") (pintype "bidirectional"))
      (node (ref "U1") (pin "72") (pinfunction "PA13/JTMS/SWDIO_72") (pintype "bidirectional"))
    )
    (net (code "54") (name "LCD_BL") (class "Default")
      (node (ref "R13") (pin "1") (pinfunction "1_1") (pintype "passive"))
      (node (ref "U1") (pin "44") (pinfunction "PE13/FSMC_D10/TIM1_CH3_44") (pintype "bidirectional"))
    )
    (net (code "55") (name "LCD_CS") (class "Default")
      (node (ref "R6") (pin "1") (pinfunction "1_1") (pintype "passive"))
      (node (ref "U$10") (pin "P31") (pinfunction "CS_P31") (pintype "bidirectional"))
      (node (ref "U1") (pin "98") (pinfunction "PE1/FSMC_NBL1/DCMI_D3_98") (pintype "bidirectional"))
    )
    (net (code "56") (name "LCD_DB0") (class "Default")
      (node (ref "U$10") (pin "P27") (pinfunction "DB0_P27") (pintype "bidirectional"))
      (node (ref "U1") (pin "81") (pinfunction "PD0/FSMC_D2/CAN1_RX_81") (pintype "bidirectional"))
    )
    (net (code "57") (name "LCD_DB1") (class "Default")
      (node (ref "U$10") (pin "P26") (pinfunction "DB1_P26") (pintype "bidirectional"))
      (node (ref "U1") (pin "82") (pinfunction "PD1/FSMC_D3/CAN1_TX_82") (pintype "bidirectional"))
    )
    (net (code "58") (name "LCD_DB2") (class "Default")
      (node (ref "U$10") (pin "P25") (pinfunction "DB2_P25") (pintype "bidirectional"))
      (node (ref "U1") (pin "83") (pinfunction "PD2/USART5_RX/SDIO_CMD/DCMI_D11_83") (pintype "bidirectional"))
    )
    (net (code "59") (name "LCD_DB3") (class "Default")
      (node (ref "U$10") (pin "P24") (pinfunction "DB3_P24") (pintype "bidirectional"))
      (node (ref "U1") (pin "84") (pinfunction "PD3/FSMC_CLK/USART2_CTS_84") (pintype "bidirectional"))
    )
    (net (code "60") (name "LCD_DB4") (class "Default")
      (node (ref "U$10") (pin "P23") (pinfunction "DB4_P23") (pintype "bidirectional"))
      (node (ref "U1") (pin "85") (pinfunction "PD4/FSMC_NOE/USART2_RTS_85") (pintype "bidirectional"))
    )
    (net (code "61") (name "LCD_DB5") (class "Default")
      (node (ref "U$10") (pin "P22") (pinfunction "DB5_P22") (pintype "bidirectional"))
      (node (ref "U1") (pin "86") (pinfunction "PD5/FSMC_NWE/USART2_TX_86") (pintype "bidirectional"))
    )
    (net (code "62") (name "LCD_DB6") (class "Default")
      (node (ref "U$10") (pin "P21") (pinfunction "DB6_P21") (pintype "bidirectional"))
      (node (ref "U1") (pin "87") (pinfunction "PD6/FSMC_NWAIT/USART2_RX_87") (pintype "bidirectional"))
    )
    (net (code "63") (name "LCD_DB7") (class "Default")
      (node (ref "U$10") (pin "P20") (pinfunction "DB7_P20") (pintype "bidirectional"))
      (node (ref "U1") (pin "88") (pinfunction "PD7/FSMC_NE1/FSMC_NCE2_88") (pintype "bidirectional"))
    )
    (net (code "64") (name "LCD_DB8") (class "Default")
      (node (ref "U$10") (pin "P19") (pinfunction "DB8_P19") (pintype "bidirectional"))
      (node (ref "U1") (pin "55") (pinfunction "PD8/FSMC_D13/USART3_TX_55") (pintype "bidirectional"))
    )
    (net (code "65") (name "LCD_DB9") (class "Default")
      (node (ref "U$10") (pin "P18") (pinfunction "DB9_P18") (pintype "bidirectional"))
      (node (ref "U1") (pin "56") (pinfunction "PD9/FSMC_D14/USART3_RX_56") (pintype "bidirectional"))
    )
    (net (code "66") (name "LCD_DB10") (class "Default")
      (node (ref "U$10") (pin "P17") (pinfunction "DB10_P17") (pintype "bidirectional"))
      (node (ref "U1") (pin "57") (pinfunction "PD10/FSMC_D15_57") (pintype "bidirectional"))
    )
    (net (code "67") (name "LCD_DB11") (class "Default")
      (node (ref "U$10") (pin "P16") (pinfunction "DB11_P16") (pintype "bidirectional"))
      (node (ref "U1") (pin "58") (pinfunction "PD11/FSMC_A16/USART3_CTS_58") (pintype "bidirectional"))
    )
    (net (code "68") (name "LCD_DB12") (class "Default")
      (node (ref "U$10") (pin "P15") (pinfunction "DB12_P15") (pintype "bidirectional"))
      (node (ref "U1") (pin "59") (pinfunction "PD12/FSMC_A17/TIM4_CH1/USART3_RTS_59") (pintype "bidirectional"))
    )
    (net (code "69") (name "LCD_DB13") (class "Default")
      (node (ref "U$10") (pin "P14") (pinfunction "DB13_P14") (pintype "bidirectional"))
      (node (ref "U1") (pin "60") (pinfunction "PD13/FSMC_A18/TIM4_CH2_60") (pintype "bidirectional"))
    )
    (net (code "70") (name "LCD_DB14") (class "Default")
      (node (ref "U$10") (pin "P13") (pinfunction "DB14_P13") (pintype "bidirectional"))
      (node (ref "U1") (pin "61") (pinfunction "PD14/FSMC_D0/TIM4_CH3_61") (pintype "bidirectional"))
    )
    (net (code "71") (name "LCD_DB15") (class "Default")
      (node (ref "U$10") (pin "P12") (pinfunction "DB15_P12") (pintype "bidirectional"))
      (node (ref "U1") (pin "62") (pinfunction "PD15/FSMC_D1/TIM4_CH4_62") (pintype "bidirectional"))
    )
    (net (code "72") (name "LCD_RD") (class "Default")
      (node (ref "R9") (pin "1") (pinfunction "1_1") (pintype "passive"))
      (node (ref "U$10") (pin "P28") (pinfunction "RD_P28") (pintype "bidirectional"))
      (node (ref "U1") (pin "3") (pinfunction "PE4/FSMC_A20/DCMI_D4_3") (pintype "bidirectional"))
    )
    (net (code "73") (name "LCD_RESET") (class "Default")
      (node (ref "R11") (pin "1") (pinfunction "1_1") (pintype "passive"))
      (node (ref "U$10") (pin "P11") (pinfunction "RESET_P11") (pintype "bidirectional"))
      (node (ref "U1") (pin "67") (pinfunction "PA8/MCO1/TIM1_CH1/I2C3_SCL_67") (pintype "bidirectional"))
    )
    (net (code "74") (name "LCD_RS") (class "Default")
      (node (ref "R7") (pin "1") (pinfunction "1_1") (pintype "passive"))
      (node (ref "U$10") (pin "P30") (pinfunction "RS_P30") (pintype "bidirectional"))
      (node (ref "U1") (pin "1") (pinfunction "PE2/FSMC_A23/ETH_MII_TXD3_1") (pintype "bidirectional"))
    )
    (net (code "75") (name "LCD_WR") (class "Default")
      (node (ref "R8") (pin "1") (pinfunction "1_1") (pintype "passive"))
      (node (ref "U$10") (pin "P29") (pinfunction "WR_P29") (pintype "bidirectional"))
      (node (ref "U1") (pin "2") (pinfunction "PE3/FSMC_A19_2") (pintype "bidirectional"))
    )
    (net (code "76") (name "LCD_X+") (class "Default")
      (node (ref "U$10") (pin "P38") (pinfunction "X+_P38") (pintype "bidirectional"))
      (node (ref "U1") (pin "36") (pinfunction "PB1/TIM3_CH4/ADC12_IN9_36") (pintype "bidirectional"))
    )
    (net (code "77") (name "LCD_X-") (class "Default")
      (node (ref "U$10") (pin "P36") (pinfunction "X-_P36") (pintype "bidirectional"))
      (node (ref "U1") (pin "51") (pinfunction "PB12/CAN2_RX_51") (pintype "bidirectional"))
    )
    (net (code "78") (name "LCD_Y+") (class "Default")
      (node (ref "U$10") (pin "P37") (pinfunction "Y+_P37") (pintype "bidirectional"))
      (node (ref "U1") (pin "35") (pinfunction "PB0/TIM3_CH3/ADC12_IN8_35") (pintype "bidirectional"))
    )
    (net (code "79") (name "LCD_Y-") (class "Default")
      (node (ref "U$10") (pin "P39") (pinfunction "Y-_P39") (pintype "bidirectional"))
      (node (ref "U1") (pin "54") (pinfunction "PB15/SPI2_MOSI/TIM12_CH2_54") (pintype "bidirectional"))
    )
    (net (code "80") (name "NJTRST") (class "Default")
      (node (ref "U$1") (pin "4") (pinfunction "JTRST_4") (pintype "bidirectional"))
      (node (ref "U1") (pin "90") (pinfunction "PB4/NJTRST/SPI3_MISO/TIMER2_CH2/SPI1_SCK_90") (pintype "bidirectional"))
    )
    (net (code "81") (name "NRST") (class "Default")
      (node (ref "C1") (pin "1") (pinfunction "1_1") (pintype "passive"))
      (node (ref "R1") (pin "1") (pinfunction "1_1") (pintype "passive"))
      (node (ref "SW2") (pin "P$2") (pinfunction "S2_P$2") (pintype "bidirectional"))
      (node (ref "U$1") (pin "7") (pinfunction "NRST_7") (pintype "bidirectional"))
      (node (ref "U1") (pin "14") (pinfunction "NRST_14") (pintype "bidirectional"))
    )
    (net (code "82") (name "Net-(C22-Pad2)") (class "Default")
      (node (ref "C22") (pin "2") (pinfunction "2_2") (pintype "passive"))
      (node (ref "R17") (pin "1") (pinfunction "1_1") (pintype "passive"))
    )
    (net (code "83") (name "Net-(CARD0-PadP1)") (class "Default")
      (node (ref "CARD0") (pin "P1") (pinfunction "P1_P1") (pintype "bidirectional"))
      (node (ref "CARD0") (pin "P2") (pinfunction "P2_P2") (pintype "bidirectional"))
      (node (ref "D1") (pin "C") (pinfunction "C_C") (pintype "passive"))
    )
    (net (code "84") (name "Net-(CARD0-PadP3)") (class "Default")
      (node (ref "CARD0") (pin "P3") (pinfunction "P3_P3") (pintype "bidirectional"))
      (node (ref "D2") (pin "C") (pinfunction "C_C") (pintype "passive"))
    )
    (net (code "85") (name "Net-(CARD0-PadP4)") (class "Default")
      (node (ref "CARD0") (pin "P4") (pinfunction "P4_P4") (pintype "bidirectional"))
      (node (ref "D3") (pin "C") (pinfunction "C_C") (pintype "passive"))
    )
    (net (code "86") (name "Net-(CARD0-PadP6)") (class "Default")
      (node (ref "CARD0") (pin "P6") (pinfunction "P6_P6") (pintype "bidirectional"))
      (node (ref "CARD0") (pin "P7") (pinfunction "P7_P7") (pintype "bidirectional"))
      (node (ref "D11") (pin "A") (pinfunction "A_A") (pintype "passive"))
    )
    (net (code "87") (name "Net-(CARD1-PadP1)") (class "Default")
      (node (ref "CARD1") (pin "P1") (pinfunction "P1_P1") (pintype "bidirectional"))
      (node (ref "CARD1") (pin "P2") (pinfunction "P2_P2") (pintype "bidirectional"))
      (node (ref "D4") (pin "C") (pinfunction "C_C") (pintype "passive"))
    )
    (net (code "88") (name "Net-(CARD1-PadP3)") (class "Default")
      (node (ref "CARD1") (pin "P3") (pinfunction "P3_P3") (pintype "bidirectional"))
      (node (ref "D9") (pin "C") (pinfunction "C_C") (pintype "passive"))
    )
    (net (code "89") (name "Net-(CARD1-PadP4)") (class "Default")
      (node (ref "CARD1") (pin "P4") (pinfunction "P4_P4") (pintype "bidirectional"))
      (node (ref "D10") (pin "C") (pinfunction "C_C") (pintype "passive"))
    )
    (net (code "90") (name "Net-(CARD1-PadP6)") (class "Default")
      (node (ref "CARD1") (pin "P6") (pinfunction "P6_P6") (pintype "bidirectional"))
      (node (ref "CARD1") (pin "P7") (pinfunction "P7_P7") (pintype "bidirectional"))
      (node (ref "D12") (pin "A") (pinfunction "A_A") (pintype "passive"))
    )
    (net (code "91") (name "Net-(D5-PadA)") (class "Default")
      (node (ref "D5") (pin "A") (pinfunction "A_A") (pintype "passive"))
      (node (ref "D8") (pin "C") (pinfunction "C_C") (pintype "passive"))
      (node (ref "F1") (pin "P$2") (pinfunction "P$2_P$2") (pintype "bidirectional"))
    )
    (net (code "92") (name "Net-(D6-PadA)") (class "Default")
      (node (ref "D6") (pin "A") (pinfunction "A_A") (pintype "passive"))
      (node (ref "D7") (pin "C") (pinfunction "C_C") (pintype "passive"))
      (node (ref "U$2") (pin "GND1") (pinfunction "GND1_GND1") (pintype "bidirectional"))
      (node (ref "U$2") (pin "GND2") (pinfunction "GND2_GND2") (pintype "bidirectional"))
      (node (ref "U$2") (pin "P2") (pinfunction "P2_P2") (pintype "bidirectional"))
    )
    (net (code "93") (name "Net-(D13-PadA)") (class "Default")
      (node (ref "D13") (pin "A") (pinfunction "A_A") (pintype "passive"))
      (node (ref "X3") (pin "1") (pinfunction "1_1") (pintype "input"))
    )
    (net (code "94") (name "Net-(F1-PadP$1)") (class "Default")
      (node (ref "F1") (pin "P$1") (pinfunction "P$1_P$1") (pintype "bidirectional"))
      (node (ref "U$2") (pin "P1") (pinfunction "P1_P1") (pintype "bidirectional"))
    )
    (net (code "95") (name "Net-(R13-Pad2)") (class "Default")
      (node (ref "R13") (pin "2") (pinfunction "2_2") (pintype "passive"))
      (node (ref "R14") (pin "2") (pinfunction "2_2") (pintype "passive"))
      (node (ref "U4") (pin "1") (pinfunction "1_1") (pintype "bidirectional"))
    )
    (net (code "96") (name "Net-(U$10-IM0)") (class "Default")
      (node (ref "R10") (pin "2") (pinfunction "2_2") (pintype "passive"))
      (node (ref "U$10") (pin "P10") (pinfunction "IM0_P10") (pintype "bidirectional"))
    )
    (net (code "97") (name "Net-(U$10-LED1)") (class "Default")
      (node (ref "U$10") (pin "P4") (pinfunction "LED4_P4") (pintype "bidirectional"))
      (node (ref "U$10") (pin "P5") (pinfunction "LED3_P5") (pintype "bidirectional"))
      (node (ref "U$10") (pin "P6") (pinfunction "LED2_P6") (pintype "bidirectional"))
      (node (ref "U$10") (pin "P7") (pinfunction "LED1_P7") (pintype "bidirectional"))
      (node (ref "U4") (pin "3") (pinfunction "3_3") (pintype "bidirectional"))
    )
    (net (code "98") (name "Net-(U$10-LEDA)") (class "Default")
      (node (ref "R12") (pin "2") (pinfunction "2_2") (pintype "passive"))
      (node (ref "U$10") (pin "P3") (pinfunction "LEDA_P3") (pintype "bidirectional"))
    )
    (net (code "99") (name "Net-(U1-VCAP_1)") (class "Default")
      (node (ref "C19") (pin "1") (pinfunction "1_1") (pintype "passive"))
      (node (ref "U1") (pin "49") (pinfunction "VCAP_1_49") (pintype "bidirectional"))
    )
    (net (code "100") (name "Net-(U1-VCAP_2)") (class "Default")
      (node (ref "C20") (pin "1") (pinfunction "1_1") (pintype "passive"))
      (node (ref "U1") (pin "73") (pinfunction "VCAP_2_73") (pintype "bidirectional"))
    )
    (net (code "101") (name "Net-(U1-VDDA)") (class "Default")
      (node (ref "L1") (pin "2") (pinfunction "2_2") (pintype "passive"))
      (node (ref "U1") (pin "21") (pinfunction "VREF+_21") (pintype "bidirectional"))
      (node (ref "U1") (pin "22") (pinfunction "VDDA_22") (pintype "bidirectional"))
    )
    (net (code "102") (name "Net-(U3-+IN)") (class "Default")
      (node (ref "C21") (pin "1") (pinfunction "1_1") (pintype "passive"))
      (node (ref "U3") (pin "2") (pinfunction "BYPASS_2") (pintype "bidirectional"))
      (node (ref "U3") (pin "3") (pinfunction "+IN_3") (pintype "bidirectional"))
    )
    (net (code "103") (name "Net-(U3--IN)") (class "Default")
      (node (ref "R17") (pin "2") (pinfunction "2_2") (pintype "passive"))
      (node (ref "U3") (pin "4") (pinfunction "-IN_4") (pintype "bidirectional"))
    )
    (net (code "104") (name "Net-(U3-VO1)") (class "Default")
      (node (ref "U3") (pin "5") (pinfunction "VO1_5") (pintype "bidirectional"))
      (node (ref "U7") (pin "P$2") (pinfunction "P$2_P$2") (pintype "bidirectional"))
    )
    (net (code "105") (name "Net-(U3-VO2)") (class "Default")
      (node (ref "U3") (pin "8") (pinfunction "VO2_8") (pintype "bidirectional"))
      (node (ref "U7") (pin "P$1") (pinfunction "P$1_P$1") (pintype "bidirectional"))
    )
    (net (code "106") (name "Net-(U5-IO1_1)") (class "Default")
      (node (ref "U5") (pin "1") (pinfunction "IO1_1_1") (pintype "bidirectional"))
      (node (ref "X3") (pin "2") (pinfunction "2_2") (pintype "input"))
    )
    (net (code "107") (name "Net-(U5-IO2_1)") (class "Default")
      (node (ref "U5") (pin "3") (pinfunction "IO2_1_3") (pintype "bidirectional"))
      (node (ref "X3") (pin "3") (pinfunction "3_3") (pintype "input"))
    )
    (net (code "108") (name "OSC32_IN") (class "Default")
      (node (ref "C15") (pin "1") (pinfunction "1_1") (pintype "passive"))
      (node (ref "U1") (pin "8") (pinfunction "PC14/OSC32_IN_8") (pintype "bidirectional"))
      (node (ref "X2") (pin "P$2") (pinfunction "XOUT_P$2") (pintype "bidirectional"))
    )
    (net (code "109") (name "OSC32_OUT") (class "Default")
      (node (ref "C14") (pin "1") (pinfunction "1_1") (pintype "passive"))
      (node (ref "U1") (pin "9") (pinfunction "PC15/OSC32_OUT_9") (pintype "bidirectional"))
      (node (ref "X2") (pin "P$1") (pinfunction "XIN_P$1") (pintype "bidirectional"))
    )
    (net (code "110") (name "OSC_IN") (class "Default")
      (node (ref "C17") (pin "1") (pinfunction "1_1") (pintype "passive"))
      (node (ref "U1") (pin "12") (pinfunction "PH0/OSC_IN_12") (pintype "bidirectional"))
      (node (ref "X1") (pin "3") (pinfunction "2_3") (pintype "passive"))
    )
    (net (code "111") (name "OSC_OUT") (class "Default")
      (node (ref "C16") (pin "1") (pinfunction "1_1") (pintype "passive"))
      (node (ref "U1") (pin "13") (pinfunction "PH1/OSC_OUT_13") (pintype "bidirectional"))
      (node (ref "X1") (pin "1") (pinfunction "1_1") (pintype "passive"))
    )
    (net (code "112") (name "PWR_BAT") (class "Default")
      (node (ref "CARD0") (pin "P8") (pinfunction "P8_P8") (pintype "bidirectional"))
      (node (ref "CARD1") (pin "P8") (pinfunction "P8_P8") (pintype "bidirectional"))
      (node (ref "U1") (pin "46") (pinfunction "PE15/FSMC_D12_46") (pintype "bidirectional"))
    )
    (net (code "113") (name "PWR_CHG") (class "Default")
      (node (ref "U$2") (pin "P3") (pinfunction "P3_P3") (pintype "bidirectional"))
      (node (ref "U1") (pin "18") (pinfunction "PC3/SPI2_MOSI/ADC123_IN13_18") (pintype "bidirectional"))
    )
    (net (code "114") (name "USB_DM") (class "Default")
      (node (ref "U1") (pin "70") (pinfunction "PA11/USART1_CTS/CAN1_RX/TIM1_CH4/USB_DM_70") (pintype "bidirectional"))
      (node (ref "U5") (pin "6") (pinfunction "IO1_2_6") (pintype "bidirectional"))
    )
    (net (code "115") (name "USB_DP") (class "Default")
      (node (ref "U1") (pin "71") (pinfunction "PA12/USART1_RTS/CAN1_TX/USB_DP_71") (pintype "bidirectional"))
      (node (ref "U5") (pin "4") (pinfunction "IO2_2_4") (pintype "bidirectional"))
    )
    (net (code "116") (name "VIN") (class "Default")
      (node (ref "D1") (pin "A") (pinfunction "A_A") (pintype "passive"))
      (node (ref "D11") (pin "C") (pinfunction "C_C") (pintype "passive"))
      (node (ref "D12") (pin "C") (pinfunction "C_C") (pintype "passive"))
      (node (ref "D13") (pin "C") (pinfunction "C_C") (pintype "passive"))
      (node (ref "D4") (pin "A") (pinfunction "A_A") (pintype "passive"))
      (node (ref "D5") (pin "C") (pinfunction "C_C") (pintype "passive"))
      (node (ref "D6") (pin "C") (pinfunction "C_C") (pintype "passive"))
      (node (ref "U6") (pin "3") (pinfunction "INPUT_3") (pintype "bidirectional"))
    )
    (net (code "117") (name "unconnected-(U$1-GND1-Pad2)") (class "Default")
      (node (ref "U$1") (pin "2") (pinfunction "GND1_2") (pintype "bidirectional"))
    )
    (net (code "118") (name "unconnected-(U$1-NC-Pad10)") (class "Default")
      (node (ref "U$1") (pin "10") (pinfunction "NC_10") (pintype "bidirectional"))
    )
    (net (code "119") (name "unconnected-(U$7-NC-Pad4)") (class "Default")
      (node (ref "U$7") (pin "4") (pinfunction "NC_4") (pintype "bidirectional"))
    )
    (net (code "120") (name "unconnected-(U$10-FMARK-PadP32)") (class "Default")
      (node (ref "U$10") (pin "P32") (pinfunction "FMARK_P32") (pintype "bidirectional"))
    )
    (net (code "121") (name "unconnected-(U$10-LCD_ID-PadP35)") (class "Default")
      (node (ref "U$10") (pin "P35") (pinfunction "LCD_ID_P35") (pintype "bidirectional"))
    )
    (net (code "122") (name "unconnected-(U$10-NC1-PadP9)") (class "Default")
      (node (ref "U$10") (pin "P9") (pinfunction "NC1_P9") (pintype "bidirectional"))
    )
    (net (code "123") (name "unconnected-(U$10-NC2-PadP1)") (class "Default")
      (node (ref "U$10") (pin "P1") (pinfunction "NC2_P1") (pintype "bidirectional"))
    )
    (net (code "124") (name "unconnected-(U1-PC2{slash}SPI2_MISO{slash}ADC123_IN12-Pad17)") (class "Default")
      (node (ref "U1") (pin "17") (pinfunction "PC2/SPI2_MISO/ADC123_IN12_17") (pintype "bidirectional"))
    )
  )
)
